# OpenROV_Topside_Interface_2_6A.net
KiCad netlist of a schematic drawn in EAGLE
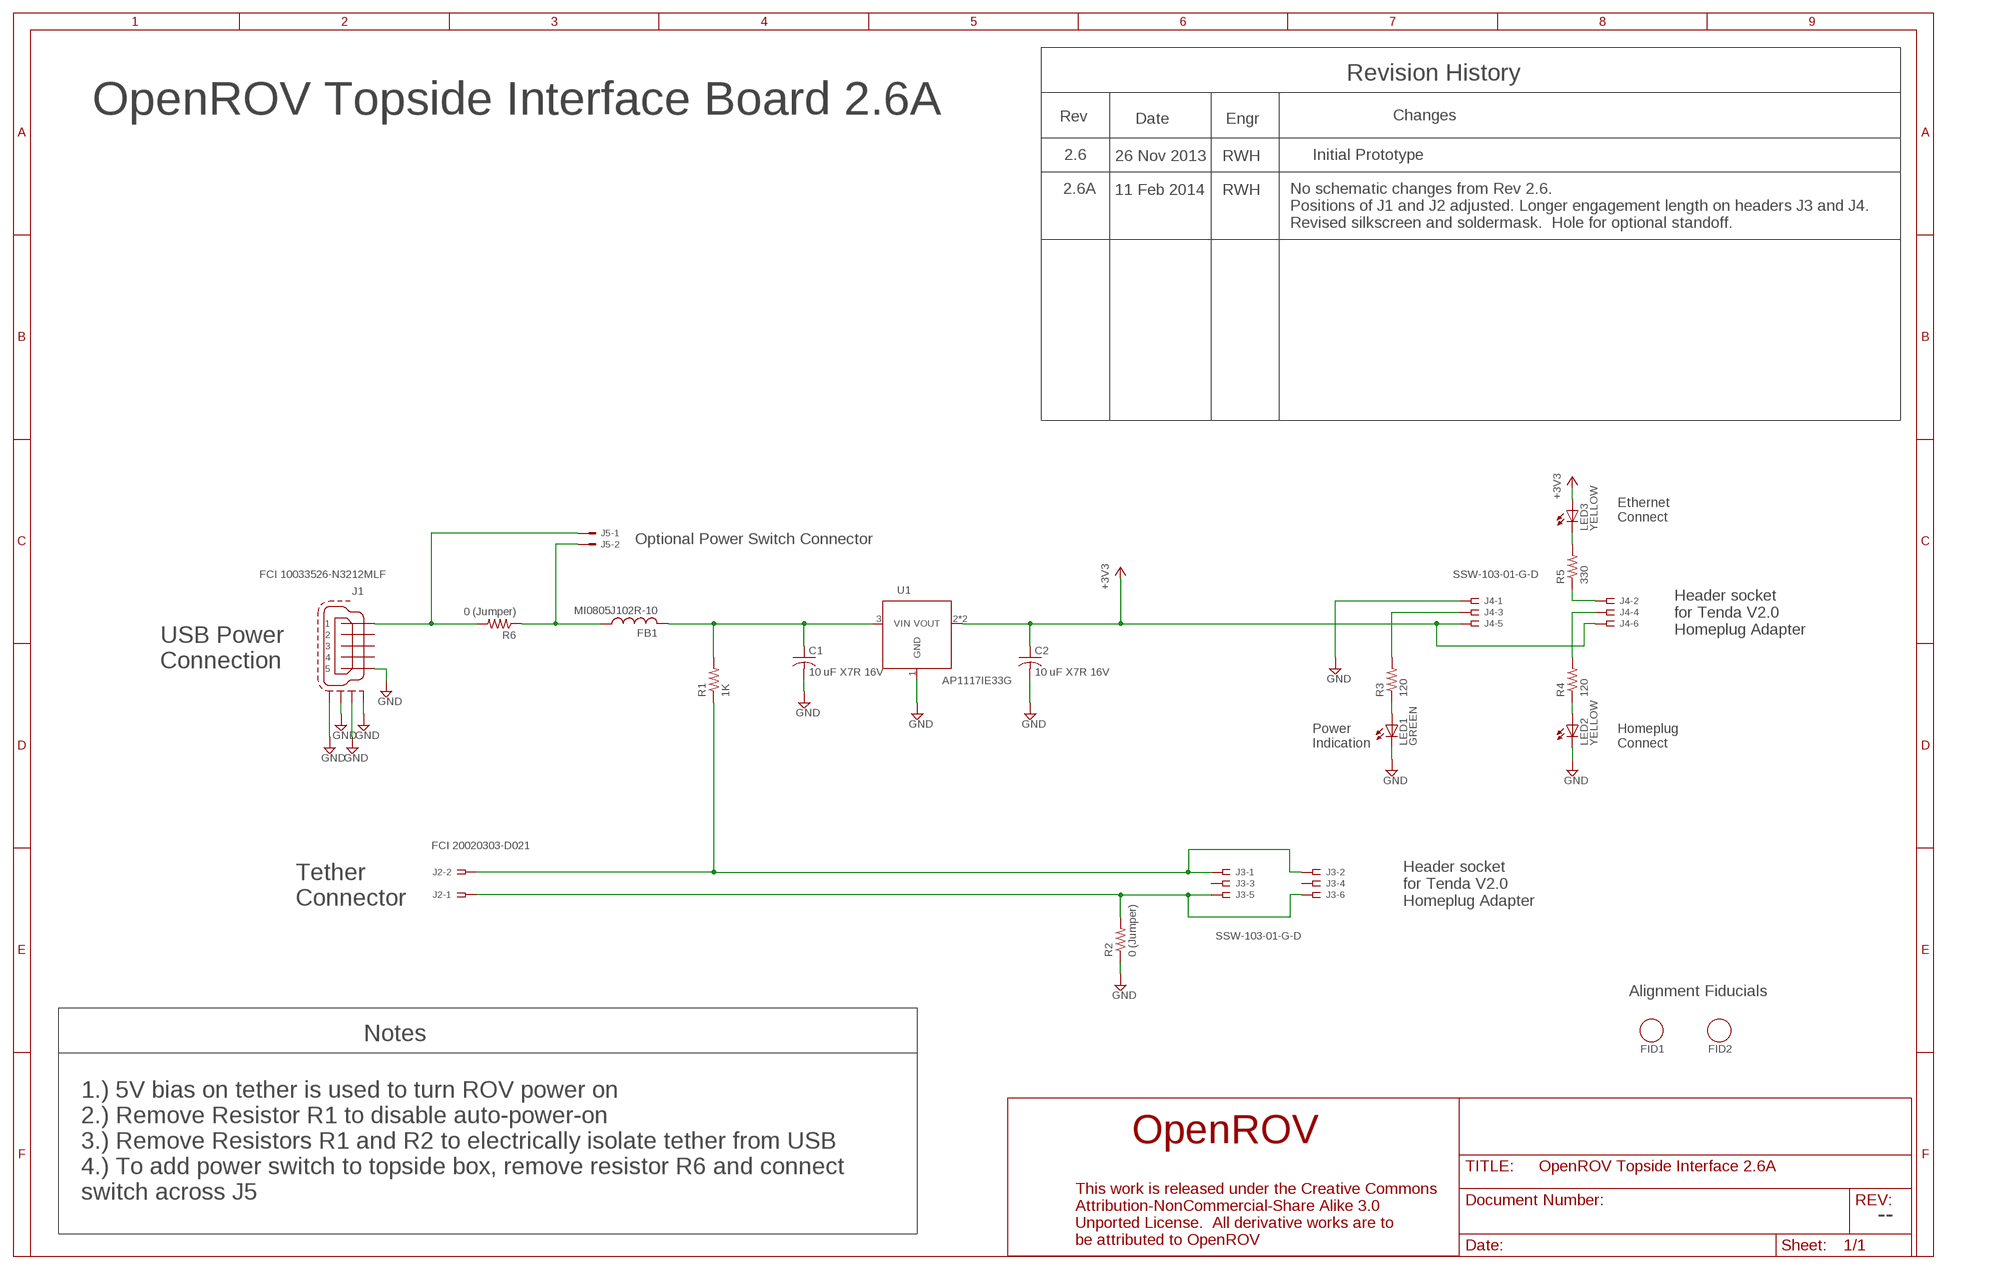
[diagram p0: schematic, sheet 1]

(export (version "E")
  (design (tool "Eeschema 10.0.6"))
  (components
    (comp (ref "C1")
      (value "10 uF X7R 16V")
      (footprint "eagle-import:R1206")
      (libsource (lib "eagle-import") (part "CAP1206"))
    )
    (comp (ref "C2")
      (value "10 uF X7R 16V")
      (footprint "eagle-import:R1206")
      (libsource (lib "eagle-import") (part "CAP1206"))
    )
    (comp (ref "FB1")
      (value "MI0805J102R-10")
      (footprint "eagle-import:R0805")
      (libsource (lib "eagle-import") (part "FERRITESIZE_0805"))
    )
    (comp (ref "FID1")
      (value "FIDUCIAL_1")
      (footprint "eagle-import:FIDUCIAL_1")
      (libsource (lib "eagle-import") (part "FIDUCIAL_1"))
    )
    (comp (ref "FID2")
      (value "FIDUCIAL_1")
      (footprint "eagle-import:FIDUCIAL_1")
      (libsource (lib "eagle-import") (part "FIDUCIAL_1"))
    )
    (comp (ref "J1")
      (value "FCI 10033526-N3212MLF")
      (footprint "eagle-import:USB_MINI-B_SM")
      (libsource (lib "eagle-import") (part "USB_MINI-BSURFACE_MOUNT"))
    )
    (comp (ref "J2")
      (value "FCI 20020303-D021")
      (footprint "eagle-import:FCI_09-381_2PL")
      (libsource (lib "eagle-import") (part "FCI_TERMINAL_BLOCK_2PL"))
    )
    (comp (ref "J3")
      (value "SSW-103-01-G-D")
      (footprint "eagle-import:SSW-103-02-S-D")
      (fields (field (name "MPN") "SSW-103-02-S-D"))
      (libsource (lib "eagle-import") (part "HDR_SOCKET_2X3"))
    )
    (comp (ref "J4")
      (value "SSW-103-01-G-D")
      (footprint "eagle-import:SSW-103-02-S-D")
      (fields (field (name "MPN") "SSW-103-02-S-D"))
      (libsource (lib "eagle-import") (part "HDR_SOCKET_2X3"))
    )
    (comp (ref "J5")
      (value "HDR_1X2X0.100-ALT_SILK")
      (footprint "eagle-import:22-23-2021_ALT_SILK")
      (libsource (lib "eagle-import") (part "HDR_1X2X0.100-ALT_SILK"))
    )
    (comp (ref "LED1")
      (value "GREEN")
      (footprint "eagle-import:LED_0805_BOTTOM_MT(OSRAM)")
      (libsource (lib "eagle-import") (part "LED-0805_BOTTOM_MT"))
    )
    (comp (ref "LED2")
      (value "YELLOW")
      (footprint "eagle-import:LED_0805_BOTTOM_MT(OSRAM)")
      (libsource (lib "eagle-import") (part "LED-0805_BOTTOM_MT"))
    )
    (comp (ref "LED3")
      (value "YELLOW")
      (footprint "eagle-import:LED_0805_BOTTOM_MT(OSRAM)")
      (libsource (lib "eagle-import") (part "LED-0805_BOTTOM_MT"))
    )
    (comp (ref "R1")
      (value "1K")
      (footprint "eagle-import:R0805")
      (libsource (lib "eagle-import") (part "RESISTOR-0805"))
    )
    (comp (ref "R2")
      (value "0 (Jumper)")
      (footprint "eagle-import:R0805")
      (libsource (lib "eagle-import") (part "RESISTOR-0805"))
    )
    (comp (ref "R3")
      (value "120")
      (footprint "eagle-import:R0805")
      (libsource (lib "eagle-import") (part "RESISTOR-0805"))
    )
    (comp (ref "R4")
      (value "120")
      (footprint "eagle-import:R0805")
      (libsource (lib "eagle-import") (part "RESISTOR-0805"))
    )
    (comp (ref "R5")
      (value "330")
      (footprint "eagle-import:R0805")
      (libsource (lib "eagle-import") (part "RESISTOR-0805"))
    )
    (comp (ref "R6")
      (value "0 (Jumper)")
      (footprint "eagle-import:R0805")
      (libsource (lib "eagle-import") (part "RESISTOR-0805"))
    )
    (comp (ref "U1")
      (value "AP1117IE33G")
      (footprint "eagle-import:SOT223")
      (libsource (lib "eagle-import") (part "AP1117SOT223"))
    )
  )
  (nets
    (net (code "1") (name "+3V3") (class "Default")
      (node (ref "C2") (pin "1") (pinfunction "1_1") (pintype "passive"))
      (node (ref "J4") (pin "5") (pinfunction "1_5") (pintype "passive"))
      (node (ref "J4") (pin "6") (pinfunction "1_6") (pintype "passive"))
      (node (ref "LED3") (pin "A") (pinfunction "A_A") (pintype "passive"))
      (node (ref "U1") (pin "2") (pinfunction "VOUT_2") (pintype "bidirectional"))
      (node (ref "U1") (pin "4") (pinfunction "VOUT_4") (pintype "bidirectional"))
    )
    (net (code "2") (name "GND") (class "Default")
      (node (ref "C1") (pin "2") (pinfunction "2_2") (pintype "passive"))
      (node (ref "C2") (pin "2") (pinfunction "2_2") (pintype "passive"))
      (node (ref "J1") (pin "5") (pinfunction "5_5") (pintype "passive"))
      (node (ref "J1") (pin "M1") (pinfunction "S1_M1") (pintype "passive"))
      (node (ref "J1") (pin "M2") (pinfunction "S2_M2") (pintype "passive"))
      (node (ref "J1") (pin "M3") (pinfunction "S3_M3") (pintype "passive"))
      (node (ref "J1") (pin "M4") (pinfunction "S4_M4") (pintype "passive"))
      (node (ref "J4") (pin "1") (pinfunction "1_1") (pintype "passive"))
      (node (ref "LED1") (pin "C") (pinfunction "C_C") (pintype "passive"))
      (node (ref "LED2") (pin "C") (pinfunction "C_C") (pintype "passive"))
      (node (ref "R2") (pin "1") (pinfunction "1_1") (pintype "passive"))
      (node (ref "U1") (pin "1") (pinfunction "GND_1") (pintype "power_in"))
    )
    (net (code "3") (name "Net-(J3B-1)") (class "Default")
      (node (ref "J2") (pin "2A") (pinfunction "1_2A") (pintype "passive"))
      (node (ref "J2") (pin "2B") (pinfunction "1_2B") (pintype "passive"))
      (node (ref "J3") (pin "1") (pinfunction "1_1") (pintype "passive"))
      (node (ref "J3") (pin "2") (pinfunction "1_2") (pintype "passive"))
      (node (ref "R1") (pin "1") (pinfunction "1_1") (pintype "passive"))
    )
    (net (code "4") (name "Net-(J3E-1)") (class "Default")
      (node (ref "J2") (pin "1A") (pinfunction "1_1A") (pintype "passive"))
      (node (ref "J2") (pin "1B") (pinfunction "1_1B") (pintype "passive"))
      (node (ref "J3") (pin "5") (pinfunction "1_5") (pintype "passive"))
      (node (ref "J3") (pin "6") (pinfunction "1_6") (pintype "passive"))
      (node (ref "R2") (pin "2") (pinfunction "2_2") (pintype "passive"))
    )
    (net (code "5") (name "Net-(J4B-1)") (class "Default")
      (node (ref "J4") (pin "2") (pinfunction "1_2") (pintype "passive"))
      (node (ref "R5") (pin "1") (pinfunction "1_1") (pintype "passive"))
    )
    (net (code "6") (name "Net-(J4C-1)") (class "Default")
      (node (ref "J4") (pin "3") (pinfunction "1_3") (pintype "passive"))
      (node (ref "R3") (pin "2") (pinfunction "2_2") (pintype "passive"))
    )
    (net (code "7") (name "Net-(J4D-1)") (class "Default")
      (node (ref "J4") (pin "4") (pinfunction "1_4") (pintype "passive"))
      (node (ref "R4") (pin "2") (pinfunction "2_2") (pintype "passive"))
    )
    (net (code "8") (name "Net-(J5A-S)") (class "Default")
      (node (ref "J1") (pin "1") (pinfunction "1_1") (pintype "passive"))
      (node (ref "J5") (pin "1") (pinfunction "S_1") (pintype "passive"))
      (node (ref "R6") (pin "2") (pinfunction "2_2") (pintype "passive"))
    )
    (net (code "9") (name "Net-(J5B-S)") (class "Default")
      (node (ref "FB1") (pin "1") (pinfunction "1_1") (pintype "passive"))
      (node (ref "J5") (pin "2") (pinfunction "S_2") (pintype "passive"))
      (node (ref "R6") (pin "1") (pinfunction "1_1") (pintype "passive"))
    )
    (net (code "10") (name "Net-(LED1-PadA)") (class "Default")
      (node (ref "LED1") (pin "A") (pinfunction "A_A") (pintype "passive"))
      (node (ref "R3") (pin "1") (pinfunction "1_1") (pintype "passive"))
    )
    (net (code "11") (name "Net-(LED2-PadA)") (class "Default")
      (node (ref "LED2") (pin "A") (pinfunction "A_A") (pintype "passive"))
      (node (ref "R4") (pin "1") (pinfunction "1_1") (pintype "passive"))
    )
    (net (code "12") (name "Net-(LED3-PadC)") (class "Default")
      (node (ref "LED3") (pin "C") (pinfunction "C_C") (pintype "passive"))
      (node (ref "R5") (pin "2") (pinfunction "2_2") (pintype "passive"))
    )
    (net (code "13") (name "Net-(U1-VIN)") (class "Default")
      (node (ref "C1") (pin "1") (pinfunction "1_1") (pintype "passive"))
      (node (ref "FB1") (pin "2") (pinfunction "2_2") (pintype "passive"))
      (node (ref "R1") (pin "2") (pinfunction "2_2") (pintype "passive"))
      (node (ref "U1") (pin "3") (pinfunction "VIN_3") (pintype "input"))
    )
    (net (code "14") (name "unconnected-(J1-Pad2)") (class "Default")
      (node (ref "J1") (pin "2") (pinfunction "2_2") (pintype "passive"))
    )
    (net (code "15") (name "unconnected-(J1-Pad3)") (class "Default")
      (node (ref "J1") (pin "3") (pinfunction "3_3") (pintype "passive"))
    )
    (net (code "16") (name "unconnected-(J1-Pad4)") (class "Default")
      (node (ref "J1") (pin "4") (pinfunction "4_4") (pintype "passive"))
    )
    (net (code "17") (name "unconnected-(J3C-1-Pad3)") (class "Default")
      (node (ref "J3") (pin "3") (pinfunction "1_3") (pintype "passive"))
    )
    (net (code "18") (name "unconnected-(J3D-1-Pad4)") (class "Default")
      (node (ref "J3") (pin "4") (pinfunction "1_4") (pintype "passive"))
    )
  )
)
